# stm32f103cb_hm_main.net
KiCad netlist of a schematic drawn in Altium Designer
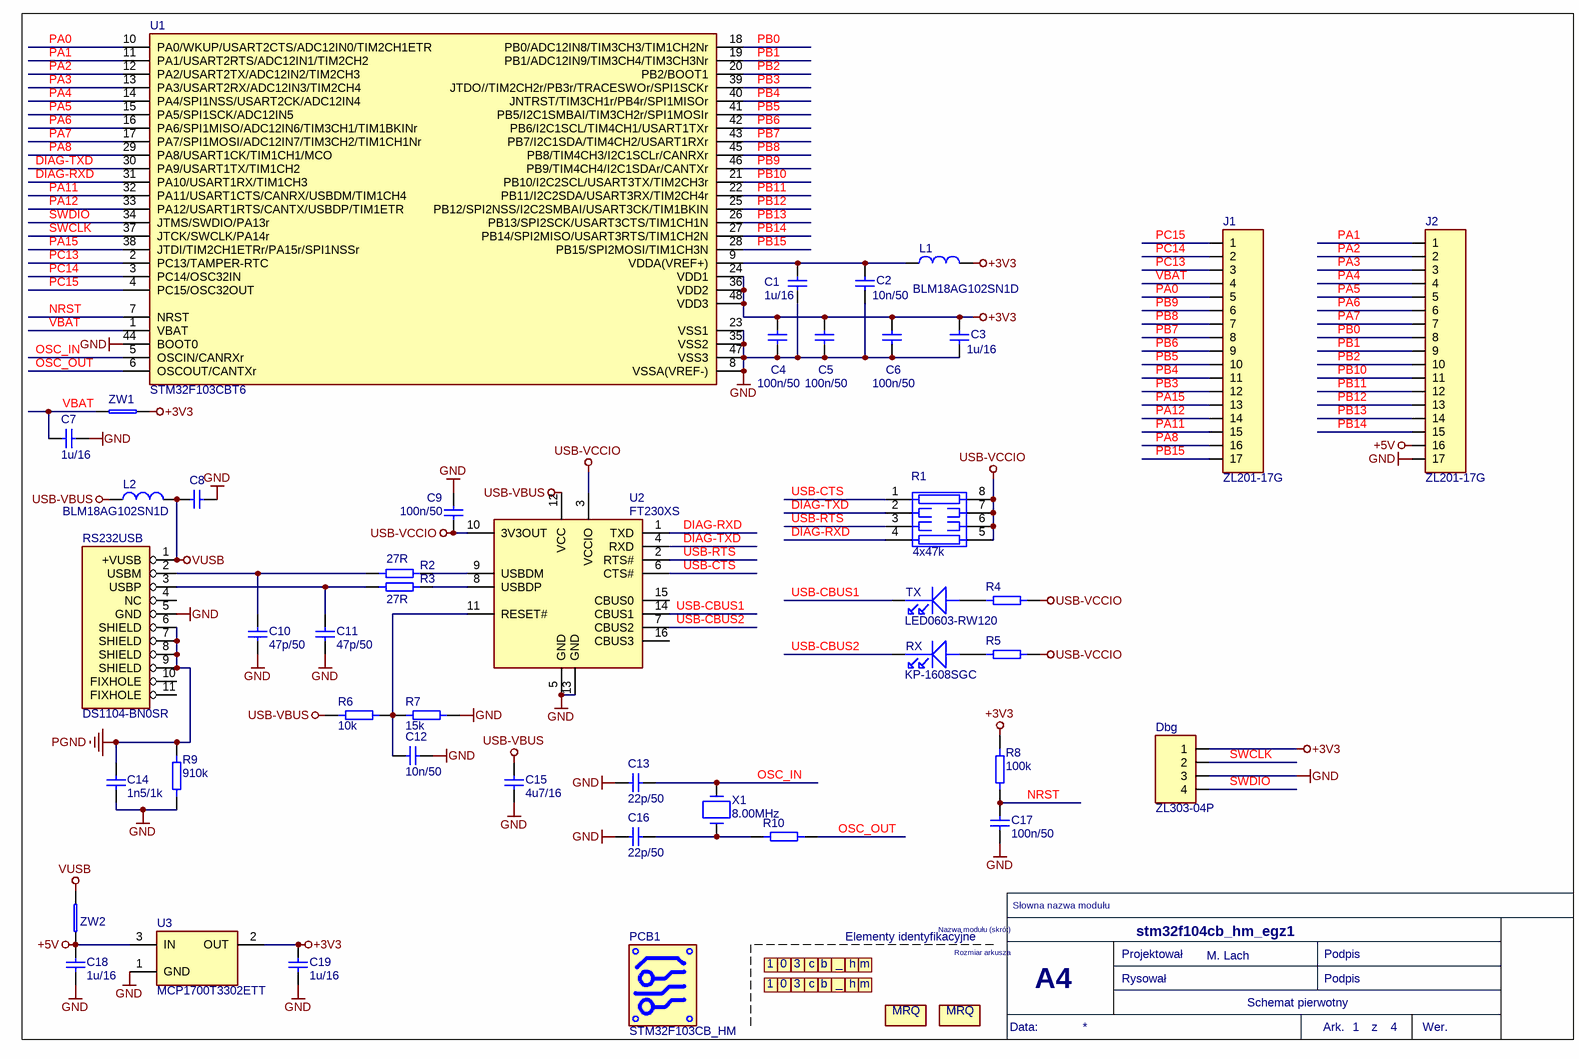
[diagram p0: stm32f103cb_hm_main.SchDoc]

(export (version "E")
  (design (tool "Eeschema 10.0.6"))
  (components
    (comp (ref "C1") (value "1u/16") (footprint "0603-IPC") (libsource (lib "PartsMySQL") (part "C")))
    (comp (ref "C2") (value "10n/50") (footprint "0603-IPC") (libsource (lib "PartsMySQL") (part "C")))
    (comp (ref "C3") (value "1u/16") (footprint "0603-IPC") (libsource (lib "PartsMySQL") (part "C")))
    (comp (ref "C4") (value "100n/50") (footprint "0603-IPC") (libsource (lib "PartsMySQL") (part "C")))
    (comp (ref "C5") (value "100n/50") (footprint "0603-IPC") (libsource (lib "PartsMySQL") (part "C")))
    (comp (ref "C6") (value "100n/50") (footprint "0603-IPC") (libsource (lib "PartsMySQL") (part "C")))
    (comp (ref "C7") (value "1u/16") (footprint "0603-IPC") (libsource (lib "PartsMySQL") (part "C")))
    (comp (ref "C8") (value "10n/50") (footprint "0603-IPC") (libsource (lib "PartsMySQL") (part "C")))
    (comp (ref "C9") (value "100n/50") (footprint "0603-IPC") (libsource (lib "PartsMySQL") (part "C")))
    (comp (ref "C10") (value "47p/50") (footprint "0603-IPC") (libsource (lib "PartsMySQL") (part "C")))
    (comp (ref "C11") (value "47p/50") (footprint "0603-IPC") (libsource (lib "PartsMySQL") (part "C")))
    (comp (ref "C12") (value "10n/50") (footprint "0603-IPC") (libsource (lib "PartsMySQL") (part "C")))
    (comp (ref "C13") (value "22p/50") (footprint "0603-IPC") (libsource (lib "PartsMySQL") (part "C")))
    (comp (ref "C14") (value "1n5/1k") (footprint "1210") (libsource (lib "PartsMySQL") (part "C")))
    (comp (ref "C15") (value "4u7/16") (footprint "0805") (libsource (lib "PartsMySQL") (part "C")))
    (comp (ref "C16") (value "22p/50") (footprint "0603-IPC") (libsource (lib "PartsMySQL") (part "C")))
    (comp (ref "C17") (value "100n/50") (footprint "0603-IPC") (libsource (lib "PartsMySQL") (part "C")))
    (comp (ref "C18") (value "1u/16") (footprint "0603-IPC") (libsource (lib "PartsMySQL") (part "C")))
    (comp (ref "C19") (value "1u/16") (footprint "0603-IPC") (libsource (lib "PartsMySQL") (part "C")))
    (comp (ref "Dbg")
      (value "ZL303-04P")
      (footprint "PLMS4S")
      (libsource (lib "PartsMySQL") (part "HEADER4"))
    )
    (comp (ref "J1")
      (value "ZL201-17G")
      (footprint "PLS17S")
      (libsource (lib "PartsMySQL") (part "HEADER17"))
    )
    (comp (ref "J2")
      (value "ZL201-17G")
      (footprint "PLS17S")
      (libsource (lib "PartsMySQL") (part "HEADER17"))
    )
    (comp (ref "L1") (value "BLM18AG102SN1D") (footprint "0603-IPC") (libsource (lib "") (part "INDUCTOR_1")))
    (comp (ref "L2")
      (value "BLM18AG102SN1D")
      (footprint "0603-IPC")
      (libsource (lib "PartsMySQL") (part "INDUCTOR"))
    )
    (comp (ref "LETTER1")
      (value "LETTER_1_1m2_m2")
      (footprint "LETTER_1_1m2_m2")
      (libsource (lib "PartsMySQL") (part "LETTER_1"))
    )
    (comp (ref "LETTER2")
      (value "LETTER_0_1m2_m2")
      (footprint "LETTER_0_1m2_m2")
      (libsource (lib "PartsMySQL") (part "LETTER_0"))
    )
    (comp (ref "LETTER3")
      (value "LETTER_3_1m2_m2")
      (footprint "LETTER_3_1m2_m2")
      (libsource (lib "PartsMySQL") (part "LETTER_3"))
    )
    (comp (ref "LETTER4")
      (value "LETTER_C_1m2_m2")
      (footprint "LETTER_C_1m2_m2")
      (libsource (lib "PartsMySQL") (part "LETTER_C"))
    )
    (comp (ref "LETTER5")
      (value "LETTER_B_1M2_M2")
      (footprint "LETTER_B_1M2_M2")
      (libsource (lib "PartsMySQL") (part "LETTER_B"))
    )
    (comp (ref "LETTER6")
      (value "LETTER_UNDERSCORE_1M2_M2")
      (footprint "LETTER_UNDERSCORE_1M2_M2")
      (libsource (lib "PartsMySQL") (part "LETTER_UNDERSCORE"))
    )
    (comp (ref "LETTER7")
      (value "LETTER_H_1M2_M2")
      (footprint "LETTER_H_1M2_M2")
      (libsource (lib "PartsMySQL") (part "LETTER_H"))
    )
    (comp (ref "LETTER8")
      (value "LETTER_M_1M2_M2")
      (footprint "LETTER_M_1M2_M2")
      (libsource (lib "PartsMySQL") (part "LETTER_M"))
    )
    (comp (ref "LETTER9")
      (value "LETTER_1_1m2_m2")
      (footprint "LETTER_1_1m2_m2")
      (libsource (lib "PartsMySQL") (part "LETTER_1"))
    )
    (comp (ref "LETTER10")
      (value "LETTER_0_1m2_m2")
      (footprint "LETTER_0_1m2_m2")
      (libsource (lib "PartsMySQL") (part "LETTER_0"))
    )
    (comp (ref "LETTER11")
      (value "LETTER_3_1m2_m2")
      (footprint "LETTER_3_1m2_m2")
      (libsource (lib "PartsMySQL") (part "LETTER_3"))
    )
    (comp (ref "LETTER12")
      (value "LETTER_C_1m2_m2")
      (footprint "LETTER_C_1m2_m2")
      (libsource (lib "PartsMySQL") (part "LETTER_C"))
    )
    (comp (ref "LETTER13")
      (value "LETTER_B_1M2_M2")
      (footprint "LETTER_B_1M2_M2")
      (libsource (lib "PartsMySQL") (part "LETTER_B"))
    )
    (comp (ref "LETTER14")
      (value "LETTER_UNDERSCORE_1M2_M2")
      (footprint "LETTER_UNDERSCORE_1M2_M2")
      (libsource (lib "PartsMySQL") (part "LETTER_UNDERSCORE"))
    )
    (comp (ref "LETTER15")
      (value "LETTER_H_1M2_M2")
      (footprint "LETTER_H_1M2_M2")
      (libsource (lib "PartsMySQL") (part "LETTER_H"))
    )
    (comp (ref "LETTER16")
      (value "LETTER_M_1M2_M2")
      (footprint "LETTER_M_1M2_M2")
      (libsource (lib "PartsMySQL") (part "LETTER_M"))
    )
    (comp (ref "LOGO1")
      (value "MRQ_2_8")
      (footprint "MRQ_2_8")
      (libsource (lib "PartsMySQL") (part "MRQLOGO"))
    )
    (comp (ref "LOGO2")
      (value "MRQ_2_8")
      (footprint "MRQ_2_8")
      (libsource (lib "PartsMySQL") (part "MRQLOGO"))
    )
    (comp (ref "PCB1") (value "STM32F103CB_HM") (libsource (lib "PartsMySQL") (part "PCBBOARD")))
    (comp (ref "R1") (value "4x47k") (footprint "1206RP") (libsource (lib "PartsMySQL") (part "DR1206")))
    (comp (ref "R2") (value "27R") (footprint "0603R") (libsource (lib "PartsMySQL") (part "R")))
    (comp (ref "R3") (value "27R") (footprint "0603R") (libsource (lib "PartsMySQL") (part "R")))
    (comp (ref "R4") (value "10k") (footprint "0603R") (libsource (lib "PartsMySQL") (part "R")))
    (comp (ref "R5") (value "10k") (footprint "0603R") (libsource (lib "PartsMySQL") (part "R")))
    (comp (ref "R6") (value "10k") (footprint "0603R") (libsource (lib "PartsMySQL") (part "R")))
    (comp (ref "R7") (value "15k") (footprint "0603R") (libsource (lib "PartsMySQL") (part "R")))
    (comp (ref "R8") (value "100k") (footprint "0603R") (libsource (lib "PartsMySQL") (part "R")))
    (comp (ref "R9") (value "910k") (footprint "2512") (libsource (lib "PartsMySQL") (part "R")))
    (comp (ref "R10") (value "220R") (footprint "0603R") (libsource (lib "PartsMySQL") (part "R")))
    (comp (ref "RS232USB")
      (value "DS1104-BN0SR")
      (footprint "USBMS1B5")
      (libsource (lib "PartsMySQL") (part "USBMS1B5"))
    )
    (comp (ref "RX") (value "KP-1608SGC") (footprint "D0603") (libsource (lib "PartsMySQL") (part "LED")))
    (comp (ref "TX") (value "LED0603-RW120") (footprint "D0603") (libsource (lib "PartsMySQL") (part "LED")))
    (comp (ref "U1")
      (value "STM32F103CBT6")
      (footprint "MS-026ABC")
      (libsource (lib "PartsMySQL") (part "STM32F103CBT6"))
    )
    (comp (ref "U2") (value "FT230XS") (footprint "MO-137AB") (libsource (lib "PartsMySQL") (part "FT230XS")))
    (comp (ref "U3")
      (value "MCP1700T3302ETT")
      (footprint "SOT23-3")
      (libsource (lib "PartsMySQL") (part "MCP1700"))
    )
    (comp (ref "X1")
      (value "8.00MHz")
      (footprint "HC49/4HSMX_THT")
      (libsource (lib "PartsMySQL") (part "CRYSTAL"))
    )
    (comp (ref "ZW1")
      (value "SHORT0805")
      (footprint "SHORT0805")
      (libsource (lib "PartsMySQL") (part "SHORT"))
    )
    (comp (ref "ZW2")
      (value "SHORT0805")
      (footprint "SHORT0805")
      (libsource (lib "PartsMySQL") (part "SHORT_NOBOM"))
    )
  )
  (nets
    (net (code "1") (name "+3V3") (class "Default")
      (node (ref "C19") (pin "1") (pinfunction "1_1") (pintype "passive"))
      (node (ref "C3") (pin "1") (pinfunction "1_1") (pintype "passive"))
      (node (ref "C4") (pin "1") (pinfunction "1_1") (pintype "passive"))
      (node (ref "C5") (pin "1") (pinfunction "1_1") (pintype "passive"))
      (node (ref "C6") (pin "1") (pinfunction "1_1") (pintype "passive"))
      (node (ref "Dbg") (pin "1") (pinfunction "1_1") (pintype "passive"))
      (node (ref "L1") (pin "2") (pinfunction "2_2") (pintype "passive"))
      (node (ref "R8") (pin "1") (pinfunction "1_1") (pintype "passive"))
      (node (ref "U1") (pin "24") (pinfunction "VDD1_24") (pintype "passive"))
      (node (ref "U1") (pin "36") (pinfunction "VDD2_36") (pintype "passive"))
      (node (ref "U1") (pin "48") (pinfunction "VDD3_48") (pintype "passive"))
      (node (ref "U3") (pin "2") (pinfunction "OUT_2") (pintype "passive"))
      (node (ref "ZW1") (pin "2") (pinfunction "2_2") (pintype "passive"))
    )
    (net (code "2") (name "+5V") (class "Default")
      (node (ref "C18") (pin "1") (pinfunction "1_1") (pintype "passive"))
      (node (ref "J2") (pin "16") (pinfunction "16_16") (pintype "passive"))
      (node (ref "U3") (pin "3") (pinfunction "IN_3") (pintype "passive"))
      (node (ref "ZW2") (pin "1") (pinfunction "1_1") (pintype "passive"))
    )
    (net (code "3") (name "/DIAG-RXD") (class "Default")
      (node (ref "R1") (pin "4") (pinfunction "R4_4") (pintype "passive"))
      (node (ref "U1") (pin "31") (pinfunction "PA10/USART1RX/TIM1CH3_31") (pintype "passive"))
      (node (ref "U2") (pin "1") (pinfunction "TXD_1") (pintype "passive"))
    )
    (net (code "4") (name "/DIAG-TXD") (class "Default")
      (node (ref "R1") (pin "2") (pinfunction "R2_2") (pintype "passive"))
      (node (ref "U1") (pin "30") (pinfunction "PA9/USART1TX/TIM1CH2_30") (pintype "passive"))
      (node (ref "U2") (pin "4") (pinfunction "RXD_4") (pintype "passive"))
    )
    (net (code "5") (name "/NRST") (class "Default")
      (node (ref "C17") (pin "1") (pinfunction "1_1") (pintype "passive"))
      (node (ref "R8") (pin "2") (pinfunction "2_2") (pintype "passive"))
      (node (ref "U1") (pin "7") (pinfunction "NRST_7") (pintype "passive"))
    )
    (net (code "6") (name "/OSC_IN") (class "Default")
      (node (ref "C13") (pin "2") (pinfunction "2_2") (pintype "passive"))
      (node (ref "U1") (pin "5") (pinfunction "OSCIN/CANRXr_5") (pintype "passive"))
      (node (ref "X1") (pin "1") (pinfunction "1_1") (pintype "passive"))
    )
    (net (code "7") (name "/OSC_OUT") (class "Default")
      (node (ref "R10") (pin "2") (pinfunction "2_2") (pintype "passive"))
      (node (ref "U1") (pin "6") (pinfunction "OSCOUT/CANTXr_6") (pintype "passive"))
    )
    (net (code "8") (name "/PA0") (class "Default")
      (node (ref "J1") (pin "5") (pinfunction "5_5") (pintype "passive"))
      (node (ref "U1") (pin "10") (pinfunction "PA0/WKUP/USART2CTS/ADC12IN0/TIM2CH1ETR_10") (pintype "passive"))
    )
    (net (code "9") (name "/PA1") (class "Default")
      (node (ref "J2") (pin "1") (pinfunction "1_1") (pintype "passive"))
      (node (ref "U1") (pin "11") (pinfunction "PA1/USART2RTS/ADC12IN1/TIM2CH2_11") (pintype "passive"))
    )
    (net (code "10") (name "/PA2") (class "Default")
      (node (ref "J2") (pin "2") (pinfunction "2_2") (pintype "passive"))
      (node (ref "U1") (pin "12") (pinfunction "PA2/USART2TX/ADC12IN2/TIM2CH3_12") (pintype "passive"))
    )
    (net (code "11") (name "/PA3") (class "Default")
      (node (ref "J2") (pin "3") (pinfunction "3_3") (pintype "passive"))
      (node (ref "U1") (pin "13") (pinfunction "PA3/USART2RX/ADC12IN3/TIM2CH4_13") (pintype "passive"))
    )
    (net (code "12") (name "/PA4") (class "Default")
      (node (ref "J2") (pin "4") (pinfunction "4_4") (pintype "passive"))
      (node (ref "U1") (pin "14") (pinfunction "PA4/SPI1NSS/USART2CK/ADC12IN4_14") (pintype "passive"))
    )
    (net (code "13") (name "/PA5") (class "Default")
      (node (ref "J2") (pin "5") (pinfunction "5_5") (pintype "passive"))
      (node (ref "U1") (pin "15") (pinfunction "PA5/SPI1SCK/ADC12IN5_15") (pintype "passive"))
    )
    (net (code "14") (name "/PA6") (class "Default")
      (node (ref "J2") (pin "6") (pinfunction "6_6") (pintype "passive"))
      (node (ref "U1") (pin "16") (pinfunction "PA6/SPI1MISO/ADC12IN6/TIM3CH1/TIM1BKINr_16") (pintype "passive"))
    )
    (net (code "15") (name "/PA7") (class "Default")
      (node (ref "J2") (pin "7") (pinfunction "7_7") (pintype "passive"))
      (node (ref "U1") (pin "17") (pinfunction "PA7/SPI1MOSI/ADC12IN7/TIM3CH2/TIM1CH1Nr_17") (pintype "passive"))
    )
    (net (code "16") (name "/PA8") (class "Default")
      (node (ref "J1") (pin "16") (pinfunction "16_16") (pintype "passive"))
      (node (ref "U1") (pin "29") (pinfunction "PA8/USART1CK/TIM1CH1/MCO_29") (pintype "passive"))
    )
    (net (code "17") (name "/PA11") (class "Default")
      (node (ref "J1") (pin "15") (pinfunction "15_15") (pintype "passive"))
      (node (ref "U1") (pin "32") (pinfunction "PA11/USART1CTS/CANRX/USBDM/TIM1CH4_32") (pintype "passive"))
    )
    (net (code "18") (name "/PA12") (class "Default")
      (node (ref "J1") (pin "14") (pinfunction "14_14") (pintype "passive"))
      (node (ref "U1") (pin "33") (pinfunction "PA12/USART1RTS/CANTX/USBDP/TIM1ETR_33") (pintype "passive"))
    )
    (net (code "19") (name "/PA15") (class "Default")
      (node (ref "J1") (pin "13") (pinfunction "13_13") (pintype "passive"))
      (node (ref "U1") (pin "38") (pinfunction "JTDI/TIM2CH1ETRr/PA15r/SPI1NSSr_38") (pintype "passive"))
    )
    (net (code "20") (name "/PB0") (class "Default")
      (node (ref "J2") (pin "8") (pinfunction "8_8") (pintype "passive"))
      (node (ref "U1") (pin "18") (pinfunction "PB0/ADC12IN8/TIM3CH3/TIM1CH2Nr_18") (pintype "passive"))
    )
    (net (code "21") (name "/PB1") (class "Default")
      (node (ref "J2") (pin "9") (pinfunction "9_9") (pintype "passive"))
      (node (ref "U1") (pin "19") (pinfunction "PB1/ADC12IN9/TIM3CH4/TIM3CH3Nr_19") (pintype "passive"))
    )
    (net (code "22") (name "/PB2") (class "Default")
      (node (ref "J2") (pin "10") (pinfunction "10_10") (pintype "passive"))
      (node (ref "U1") (pin "20") (pinfunction "PB2/BOOT1_20") (pintype "passive"))
    )
    (net (code "23") (name "/PB3") (class "Default")
      (node (ref "J1") (pin "12") (pinfunction "12_12") (pintype "passive"))
      (node (ref "U1") (pin "39") (pinfunction "JTDO//TIM2CH2r/PB3r/TRACESWOr/SPI1SCKr_39") (pintype "passive"))
    )
    (net (code "24") (name "/PB4") (class "Default")
      (node (ref "J1") (pin "11") (pinfunction "11_11") (pintype "passive"))
      (node (ref "U1") (pin "40") (pinfunction "JNTRST/TIM3CH1r/PB4r/SPI1MISOr_40") (pintype "passive"))
    )
    (net (code "25") (name "/PB5") (class "Default")
      (node (ref "J1") (pin "10") (pinfunction "10_10") (pintype "passive"))
      (node (ref "U1") (pin "41") (pinfunction "PB5/I2C1SMBAI/TIM3CH2r/SPI1MOSIr_41") (pintype "passive"))
    )
    (net (code "26") (name "/PB6") (class "Default")
      (node (ref "J1") (pin "9") (pinfunction "9_9") (pintype "passive"))
      (node (ref "U1") (pin "42") (pinfunction "PB6/I2C1SCL/TIM4CH1/USART1TXr_42") (pintype "passive"))
    )
    (net (code "27") (name "/PB7") (class "Default")
      (node (ref "J1") (pin "8") (pinfunction "8_8") (pintype "passive"))
      (node (ref "U1") (pin "43") (pinfunction "PB7/I2C1SDA/TIM4CH2/USART1RXr_43") (pintype "passive"))
    )
    (net (code "28") (name "/PB8") (class "Default")
      (node (ref "J1") (pin "7") (pinfunction "7_7") (pintype "passive"))
      (node (ref "U1") (pin "45") (pinfunction "PB8/TIM4CH3/I2C1SCLr/CANRXr_45") (pintype "passive"))
    )
    (net (code "29") (name "/PB9") (class "Default")
      (node (ref "J1") (pin "6") (pinfunction "6_6") (pintype "passive"))
      (node (ref "U1") (pin "46") (pinfunction "PB9/TIM4CH4/I2C1SDAr/CANTXr_46") (pintype "passive"))
    )
    (net (code "30") (name "/PB10") (class "Default")
      (node (ref "J2") (pin "11") (pinfunction "11_11") (pintype "passive"))
      (node (ref "U1") (pin "21") (pinfunction "PB10/I2C2SCL/USART3TX/TIM2CH3r_21") (pintype "passive"))
    )
    (net (code "31") (name "/PB11") (class "Default")
      (node (ref "J2") (pin "12") (pinfunction "12_12") (pintype "passive"))
      (node (ref "U1") (pin "22") (pinfunction "PB11/I2C2SDA/USART3RX/TIM2CH4r_22") (pintype "passive"))
    )
    (net (code "32") (name "/PB12") (class "Default")
      (node (ref "J2") (pin "13") (pinfunction "13_13") (pintype "passive"))
      (node (ref "U1") (pin "25") (pinfunction "PB12/SPI2NSS/I2C2SMBAI/USART3CK/TIM1BKIN_25") (pintype "passive"))
    )
    (net (code "33") (name "/PB13") (class "Default")
      (node (ref "J2") (pin "14") (pinfunction "14_14") (pintype "passive"))
      (node (ref "U1") (pin "26") (pinfunction "PB13/SPI2SCK/USART3CTS/TIM1CH1N_26") (pintype "passive"))
    )
    (net (code "34") (name "/PB14") (class "Default")
      (node (ref "J2") (pin "15") (pinfunction "15_15") (pintype "passive"))
      (node (ref "U1") (pin "27") (pinfunction "PB14/SPI2MISO/USART3RTS/TIM1CH2N_27") (pintype "passive"))
    )
    (net (code "35") (name "/PB15") (class "Default")
      (node (ref "J1") (pin "17") (pinfunction "17_17") (pintype "passive"))
      (node (ref "U1") (pin "28") (pinfunction "PB15/SPI2MOSI/TIM1CH3N_28") (pintype "passive"))
    )
    (net (code "36") (name "/PC13") (class "Default")
      (node (ref "J1") (pin "3") (pinfunction "3_3") (pintype "passive"))
      (node (ref "U1") (pin "2") (pinfunction "PC13/TAMPER-RTC_2") (pintype "passive"))
    )
    (net (code "37") (name "/PC14") (class "Default")
      (node (ref "J1") (pin "2") (pinfunction "2_2") (pintype "passive"))
      (node (ref "U1") (pin "3") (pinfunction "PC14/OSC32IN_3") (pintype "passive"))
    )
    (net (code "38") (name "/PC15") (class "Default")
      (node (ref "J1") (pin "1") (pinfunction "1_1") (pintype "passive"))
      (node (ref "U1") (pin "4") (pinfunction "PC15/OSC32OUT_4") (pintype "passive"))
    )
    (net (code "39") (name "/SWCLK") (class "Default")
      (node (ref "Dbg") (pin "2") (pinfunction "2_2") (pintype "passive"))
      (node (ref "U1") (pin "37") (pinfunction "JTCK/SWCLK/PA14r_37") (pintype "passive"))
    )
    (net (code "40") (name "/SWDIO") (class "Default")
      (node (ref "Dbg") (pin "4") (pinfunction "4_4") (pintype "passive"))
      (node (ref "U1") (pin "34") (pinfunction "JTMS/SWDIO/PA13r_34") (pintype "passive"))
    )
    (net (code "41") (name "/USB-CBUS1") (class "Default")
      (node (ref "TX") (pin "CATH") (pinfunction "CATH_CATH") (pintype "passive"))
      (node (ref "U2") (pin "14") (pinfunction "CBUS1_14") (pintype "passive"))
    )
    (net (code "42") (name "/USB-CBUS2") (class "Default")
      (node (ref "RX") (pin "CATH") (pinfunction "CATH_CATH") (pintype "passive"))
      (node (ref "U2") (pin "7") (pinfunction "CBUS2_7") (pintype "passive"))
    )
    (net (code "43") (name "/USB-CTS") (class "Default")
      (node (ref "R1") (pin "1") (pinfunction "R1_1") (pintype "passive"))
      (node (ref "U2") (pin "6") (pinfunction "CTS#_6") (pintype "passive"))
    )
    (net (code "44") (name "/USB-RTS") (class "Default")
      (node (ref "R1") (pin "3") (pinfunction "R3_3") (pintype "passive"))
      (node (ref "U2") (pin "2") (pinfunction "RTS#_2") (pintype "passive"))
    )
    (net (code "45") (name "/VBAT") (class "Default")
      (node (ref "C7") (pin "1") (pinfunction "1_1") (pintype "passive"))
      (node (ref "J1") (pin "4") (pinfunction "4_4") (pintype "passive"))
      (node (ref "U1") (pin "1") (pinfunction "VBAT_1") (pintype "passive"))
      (node (ref "ZW1") (pin "1") (pinfunction "1_1") (pintype "passive"))
    )
    (net (code "46") (name "GND") (class "Default")
      (node (ref "C1") (pin "2") (pinfunction "2_2") (pintype "passive"))
      (node (ref "C10") (pin "2") (pinfunction "2_2") (pintype "passive"))
      (node (ref "C11") (pin "2") (pinfunction "2_2") (pintype "passive"))
      (node (ref "C12") (pin "1") (pinfunction "1_1") (pintype "passive"))
      (node (ref "C13") (pin "1") (pinfunction "1_1") (pintype "passive"))
      (node (ref "C14") (pin "2") (pinfunction "2_2") (pintype "passive"))
      (node (ref "C15") (pin "2") (pinfunction "2_2") (pintype "passive"))
      (node (ref "C16") (pin "1") (pinfunction "1_1") (pintype "passive"))
      (node (ref "C17") (pin "2") (pinfunction "2_2") (pintype "passive"))
      (node (ref "C18") (pin "2") (pinfunction "2_2") (pintype "passive"))
      (node (ref "C19") (pin "2") (pinfunction "2_2") (pintype "passive"))
      (node (ref "C2") (pin "2") (pinfunction "2_2") (pintype "passive"))
      (node (ref "C3") (pin "2") (pinfunction "2_2") (pintype "passive"))
      (node (ref "C4") (pin "2") (pinfunction "2_2") (pintype "passive"))
      (node (ref "C5") (pin "2") (pinfunction "2_2") (pintype "passive"))
      (node (ref "C6") (pin "2") (pinfunction "2_2") (pintype "passive"))
      (node (ref "C7") (pin "2") (pinfunction "2_2") (pintype "passive"))
      (node (ref "C8") (pin "1") (pinfunction "1_1") (pintype "passive"))
      (node (ref "C9") (pin "1") (pinfunction "1_1") (pintype "passive"))
      (node (ref "Dbg") (pin "3") (pinfunction "3_3") (pintype "passive"))
      (node (ref "J2") (pin "17") (pinfunction "17_17") (pintype "passive"))
      (node (ref "R7") (pin "2") (pinfunction "2_2") (pintype "passive"))
      (node (ref "R9") (pin "2") (pinfunction "2_2") (pintype "passive"))
      (node (ref "RS232USB") (pin "5") (pinfunction "GND_5") (pintype "passive"))
      (node (ref "U1") (pin "23") (pinfunction "VSS1_23") (pintype "passive"))
      (node (ref "U1") (pin "35") (pinfunction "VSS2_35") (pintype "passive"))
      (node (ref "U1") (pin "44") (pinfunction "BOOT0_44") (pintype "passive"))
      (node (ref "U1") (pin "47") (pinfunction "VSS3_47") (pintype "passive"))
      (node (ref "U1") (pin "8") (pinfunction "VSSA(VREF-)_8") (pintype "passive"))
      (node (ref "U2") (pin "13") (pinfunction "GND_13") (pintype "passive"))
      (node (ref "U2") (pin "5") (pinfunction "GND_5") (pintype "passive"))
      (node (ref "U3") (pin "1") (pinfunction "GND_1") (pintype "passive"))
    )
    (net (code "47") (name "Net-(C16-Pad2)") (class "Default")
      (node (ref "C16") (pin "2") (pinfunction "2_2") (pintype "passive"))
      (node (ref "R10") (pin "1") (pinfunction "1_1") (pintype "passive"))
      (node (ref "X1") (pin "2") (pinfunction "2_2") (pintype "passive"))
    )
    (net (code "48") (name "Net-(R4-Pad1)") (class "Default")
      (node (ref "R4") (pin "1") (pinfunction "1_1") (pintype "passive"))
      (node (ref "TX") (pin "ANOD") (pinfunction "ANOD_ANOD") (pintype "passive"))
    )
    (net (code "49") (name "Net-(R5-Pad1)") (class "Default")
      (node (ref "R5") (pin "1") (pinfunction "1_1") (pintype "passive"))
      (node (ref "RX") (pin "ANOD") (pinfunction "ANOD_ANOD") (pintype "passive"))
    )
    (net (code "50") (name "Net-(RS232USB-USBM)") (class "Default")
      (node (ref "C10") (pin "1") (pinfunction "1_1") (pintype "passive"))
      (node (ref "R2") (pin "1") (pinfunction "1_1") (pintype "passive"))
      (node (ref "RS232USB") (pin "2") (pinfunction "USBM_2") (pintype "passive"))
    )
    (net (code "51") (name "Net-(RS232USB-USBP)") (class "Default")
      (node (ref "C11") (pin "1") (pinfunction "1_1") (pintype "passive"))
      (node (ref "R3") (pin "1") (pinfunction "1_1") (pintype "passive"))
      (node (ref "RS232USB") (pin "3") (pinfunction "USBP_3") (pintype "passive"))
    )
    (net (code "52") (name "Net-(U1-VDDA(VREF+))") (class "Default")
      (node (ref "C1") (pin "1") (pinfunction "1_1") (pintype "passive"))
      (node (ref "C2") (pin "1") (pinfunction "1_1") (pintype "passive"))
      (node (ref "L1") (pin "1") (pinfunction "1_1") (pintype "passive"))
      (node (ref "U1") (pin "9") (pinfunction "VDDA(VREF+)_9") (pintype "passive"))
    )
    (net (code "53") (name "Net-(U2-RESET#)") (class "Default")
      (node (ref "C12") (pin "2") (pinfunction "2_2") (pintype "passive"))
      (node (ref "R6") (pin "2") (pinfunction "2_2") (pintype "passive"))
      (node (ref "R7") (pin "1") (pinfunction "1_1") (pintype "passive"))
      (node (ref "U2") (pin "11") (pinfunction "RESET#_11") (pintype "passive"))
    )
    (net (code "54") (name "Net-(U2-USBDM)") (class "Default")
      (node (ref "R2") (pin "2") (pinfunction "2_2") (pintype "passive"))
      (node (ref "U2") (pin "9") (pinfunction "USBDM_9") (pintype "passive"))
    )
    (net (code "55") (name "Net-(U2-USBDP)") (class "Default")
      (node (ref "R3") (pin "2") (pinfunction "2_2") (pintype "passive"))
      (node (ref "U2") (pin "8") (pinfunction "USBDP_8") (pintype "passive"))
    )
    (net (code "56") (name "PGND") (class "Default")
      (node (ref "C14") (pin "1") (pinfunction "1_1") (pintype "passive"))
      (node (ref "R9") (pin "1") (pinfunction "1_1") (pintype "passive"))
      (node (ref "RS232USB") (pin "6") (pinfunction "SHIELD_6") (pintype "passive"))
      (node (ref "RS232USB") (pin "7") (pinfunction "SHIELD_7") (pintype "passive"))
      (node (ref "RS232USB") (pin "8") (pinfunction "SHIELD_8") (pintype "passive"))
      (node (ref "RS232USB") (pin "9") (pinfunction "SHIELD_9") (pintype "passive"))
    )
    (net (code "57") (name "USB-VBUS") (class "Default")
      (node (ref "C15") (pin "1") (pinfunction "1_1") (pintype "passive"))
      (node (ref "L2") (pin "2") (pinfunction "2_2") (pintype "passive"))
      (node (ref "R6") (pin "1") (pinfunction "1_1") (pintype "passive"))
      (node (ref "U2") (pin "12") (pinfunction "VCC_12") (pintype "passive"))
    )
    (net (code "58") (name "USB-VCCIO") (class "Default")
      (node (ref "C9") (pin "2") (pinfunction "2_2") (pintype "passive"))
      (node (ref "R1") (pin "5") (pinfunction "R5_5") (pintype "passive"))
      (node (ref "R1") (pin "6") (pinfunction "R6_6") (pintype "passive"))
      (node (ref "R1") (pin "7") (pinfunction "R7_7") (pintype "passive"))
      (node (ref "R1") (pin "8") (pinfunction "R8_8") (pintype "passive"))
      (node (ref "R4") (pin "2") (pinfunction "2_2") (pintype "passive"))
      (node (ref "R5") (pin "2") (pinfunction "2_2") (pintype "passive"))
      (node (ref "U2") (pin "10") (pinfunction "3V3OUT_10") (pintype "passive"))
      (node (ref "U2") (pin "3") (pinfunction "VCCIO_3") (pintype "passive"))
    )
    (net (code "59") (name "VUSB") (class "Default")
      (node (ref "C8") (pin "2") (pinfunction "2_2") (pintype "passive"))
      (node (ref "L2") (pin "1") (pinfunction "1_1") (pintype "passive"))
      (node (ref "RS232USB") (pin "1") (pinfunction "+VUSB_1") (pintype "passive"))
      (node (ref "ZW2") (pin "2") (pinfunction "2_2") (pintype "passive"))
    )
    (net (code "60") (name "unconnected-(RS232USB-FIXHOLE-Pad10)") (class "Default")
      (node (ref "RS232USB") (pin "10") (pinfunction "FIXHOLE_10") (pintype "passive"))
    )
    (net (code "61") (name "unconnected-(RS232USB-FIXHOLE-Pad11)") (class "Default")
      (node (ref "RS232USB") (pin "11") (pinfunction "FIXHOLE_11") (pintype "passive"))
    )
    (net (code "62") (name "unconnected-(RS232USB-NC-Pad4)") (class "Default")
      (node (ref "RS232USB") (pin "4") (pinfunction "NC_4") (pintype "passive"))
    )
    (net (code "63") (name "unconnected-(U2-CBUS0-Pad15)") (class "Default")
      (node (ref "U2") (pin "15") (pinfunction "CBUS0_15") (pintype "passive"))
    )
    (net (code "64") (name "unconnected-(U2-CBUS3-Pad16)") (class "Default")
      (node (ref "U2") (pin "16") (pinfunction "CBUS3_16") (pintype "passive"))
    )
  )
)
